# MotorControlBoard_A4988.net
KiCad netlist of a schematic drawn in Altium Designer
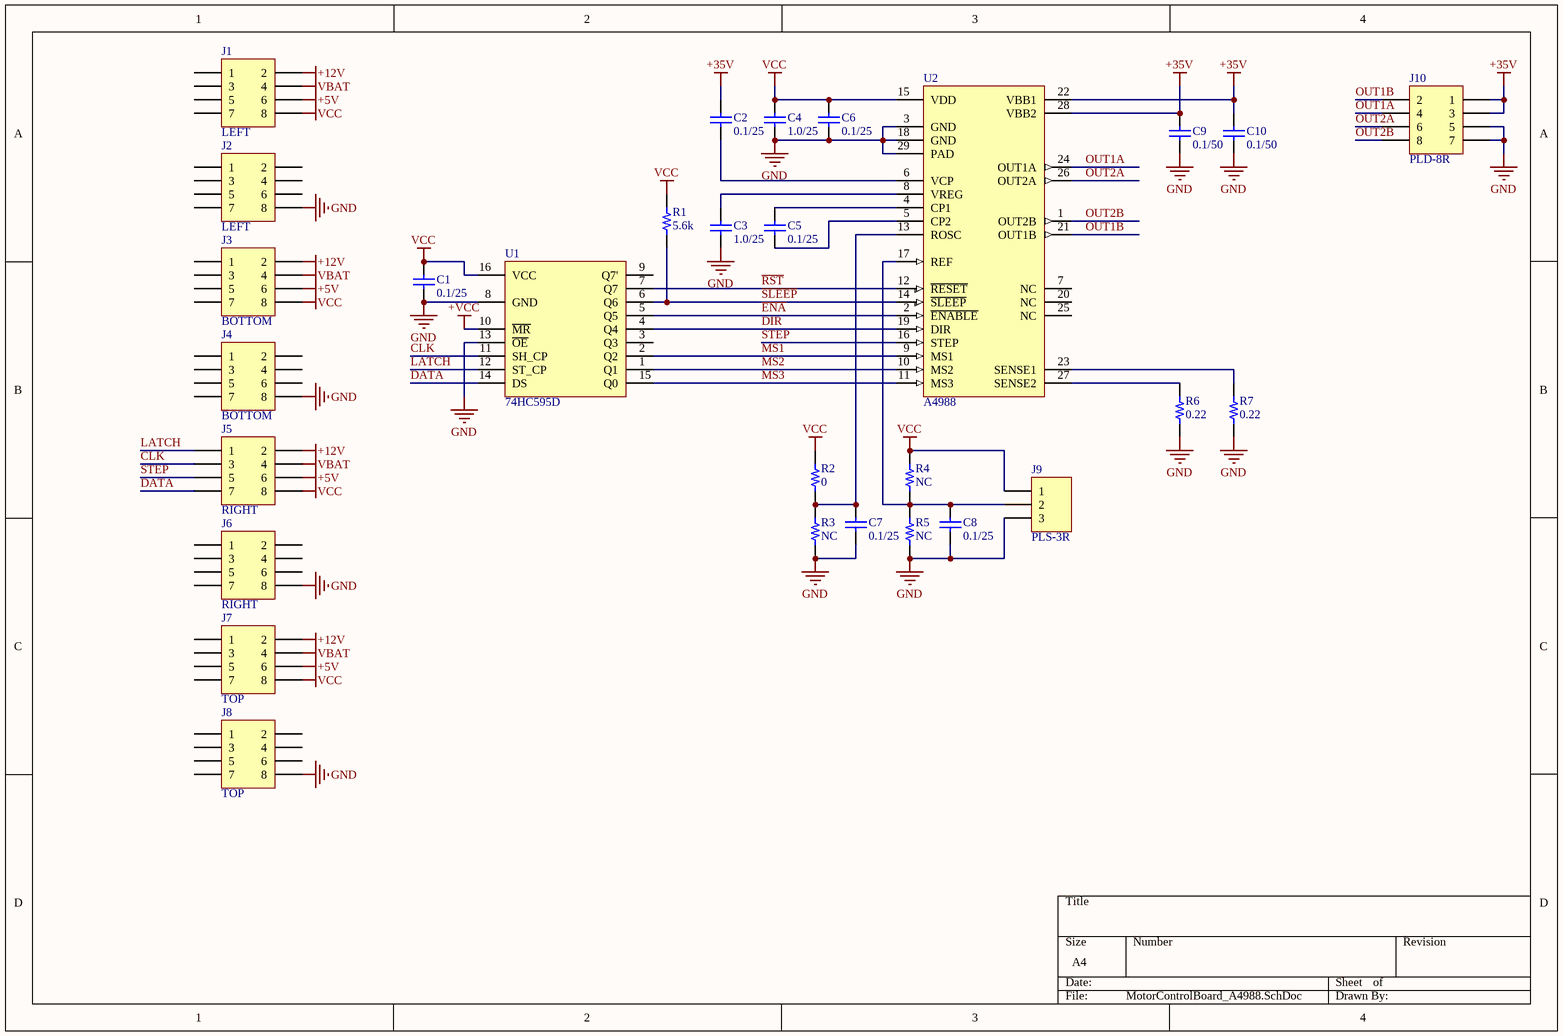
[diagram p0: MotorControlBoard_A4988.SchDoc]

(export (version "E")
  (design (tool "Eeschema 10.0.6"))
  (components
    (comp (ref "C1")
      (value "0.1/25")
      (footprint "CAP0603")
      (description "Ceramic chip capacitor 0603")
      (fields
        (field (name "PARTNUMBER") "CAP0603")
        (field (name "VOLTAGE") "25")
        (field (name "AUTHOR") "oiezhov")
      )
      (libsource (lib "Library") (part "Capacitor"))
    )
    (comp (ref "C2")
      (value "0.1/25")
      (footprint "CAP0402")
      (description "Ceramic chip capacitor 0402")
      (fields
        (field (name "PARTNUMBER") "CAP0402")
        (field (name "VOLTAGE") "25")
        (field (name "AUTHOR") "oiezhov")
      )
      (libsource (lib "Library") (part "Capacitor"))
    )
    (comp (ref "C3")
      (value "1.0/25")
      (footprint "CAP0402")
      (description "Ceramic chip capacitor 0402")
      (fields
        (field (name "PARTNUMBER") "CAP0402")
        (field (name "VOLTAGE") "25")
        (field (name "AUTHOR") "oiezhov")
      )
      (libsource (lib "Library") (part "Capacitor"))
    )
    (comp (ref "C4")
      (value "1.0/25")
      (footprint "CAP0402")
      (description "Ceramic chip capacitor 0402")
      (fields
        (field (name "PARTNUMBER") "CAP0402")
        (field (name "VOLTAGE") "25")
        (field (name "AUTHOR") "oiezhov")
      )
      (libsource (lib "Library") (part "Capacitor"))
    )
    (comp (ref "C5")
      (value "0.1/25")
      (footprint "CAP0402")
      (description "Ceramic chip capacitor 0402")
      (fields
        (field (name "PARTNUMBER") "CAP0402")
        (field (name "VOLTAGE") "25")
        (field (name "AUTHOR") "oiezhov")
      )
      (libsource (lib "Library") (part "Capacitor"))
    )
    (comp (ref "C6")
      (value "0.1/25")
      (footprint "CAP0402")
      (description "Ceramic chip capacitor 0402")
      (fields
        (field (name "PARTNUMBER") "CAP0402")
        (field (name "VOLTAGE") "25")
        (field (name "AUTHOR") "oiezhov")
      )
      (libsource (lib "Library") (part "Capacitor"))
    )
    (comp (ref "C7")
      (value "0.1/25")
      (footprint "CAP0402")
      (description "Ceramic chip capacitor 0402")
      (fields
        (field (name "PARTNUMBER") "CAP0402")
        (field (name "VOLTAGE") "25")
        (field (name "AUTHOR") "oiezhov")
      )
      (libsource (lib "Library") (part "Capacitor"))
    )
    (comp (ref "C8")
      (value "0.1/25")
      (footprint "CAP0402")
      (description "Ceramic chip capacitor 0402")
      (fields
        (field (name "PARTNUMBER") "CAP0402")
        (field (name "VOLTAGE") "25")
        (field (name "AUTHOR") "oiezhov")
      )
      (libsource (lib "Library") (part "Capacitor"))
    )
    (comp (ref "C9")
      (value "0.1/50")
      (footprint "CAP0805")
      (description "Ceramic chip capacitor 0805")
      (fields
        (field (name "PARTNUMBER") "CAP0805")
        (field (name "VOLTAGE") "50")
        (field (name "AUTHOR") "oiezhov")
      )
      (libsource (lib "Library") (part "Capacitor"))
    )
    (comp (ref "C10")
      (value "0.1/50")
      (footprint "CAP0805")
      (description "Ceramic chip capacitor 0805")
      (fields
        (field (name "PARTNUMBER") "CAP0805")
        (field (name "VOLTAGE") "50")
        (field (name "AUTHOR") "oiezhov")
      )
      (libsource (lib "Library") (part "Capacitor"))
    )
    (comp (ref "J1")
      (value "LEFT")
      (footprint "PBDM-8")
      (description "2x4-pin header, pitch 2.54 mm")
      (fields (field (name "PARTNUMBER") "PBDM-8") (field (name "AUTHOR") "oiezhov"))
      (libsource (lib "Library") (part "8-pin dual row connector"))
    )
    (comp (ref "J2")
      (value "LEFT")
      (footprint "PBDM-8")
      (description "2x4-pin header, pitch 2.54 mm")
      (fields (field (name "PARTNUMBER") "PBDM-8") (field (name "AUTHOR") "oiezhov"))
      (libsource (lib "Library") (part "8-pin dual row connector"))
    )
    (comp (ref "J3")
      (value "BOTTOM")
      (footprint "PBDM-8")
      (description "2x4-pin header, pitch 2.54 mm")
      (fields (field (name "PARTNUMBER") "PBDM-8") (field (name "AUTHOR") "oiezhov"))
      (libsource (lib "Library") (part "8-pin dual row connector"))
    )
    (comp (ref "J4")
      (value "BOTTOM")
      (footprint "PBDM-8")
      (description "2x4-pin header, pitch 2.54 mm")
      (fields (field (name "PARTNUMBER") "PBDM-8") (field (name "AUTHOR") "oiezhov"))
      (libsource (lib "Library") (part "8-pin dual row connector"))
    )
    (comp (ref "J5")
      (value "RIGHT")
      (footprint "PBDM-8")
      (description "2x4-pin header, pitch 2.54 mm")
      (fields (field (name "PARTNUMBER") "PBDM-8") (field (name "AUTHOR") "oiezhov"))
      (libsource (lib "Library") (part "8-pin dual row connector"))
    )
    (comp (ref "J6")
      (value "RIGHT")
      (footprint "PBDM-8")
      (description "2x4-pin header, pitch 2.54 mm")
      (fields (field (name "PARTNUMBER") "PBDM-8") (field (name "AUTHOR") "oiezhov"))
      (libsource (lib "Library") (part "8-pin dual row connector"))
    )
    (comp (ref "J7")
      (value "TOP")
      (footprint "PBDM-8")
      (description "2x4-pin header, pitch 2.54 mm")
      (fields (field (name "PARTNUMBER") "PBDM-8") (field (name "AUTHOR") "oiezhov"))
      (libsource (lib "Library") (part "8-pin dual row connector"))
    )
    (comp (ref "J8")
      (value "TOP")
      (footprint "PBDM-8")
      (description "2x4-pin header, pitch 2.54 mm")
      (fields (field (name "PARTNUMBER") "PBDM-8") (field (name "AUTHOR") "oiezhov"))
      (libsource (lib "Library") (part "8-pin dual row connector"))
    )
    (comp (ref "J9")
      (value "PLS-3R")
      (footprint "PLS-3R")
      (description "3-pin angle header, pitch 2.54 mm")
      (fields (field (name "AUTHOR") "oiezhov"))
      (libsource (lib "Library") (part "3-pin connector"))
    )
    (comp (ref "J10")
      (value "PLD-8R")
      (footprint "PLD-8R")
      (description "2x4-pin angle header, pitch 2.54 mm")
      (fields (field (name "AUTHOR") "oiezhov"))
      (libsource (lib "") (part "8-pin dual row connector_1"))
    )
    (comp (ref "R1")
      (value "5.6k")
      (footprint "RES0402")
      (description "Ceramic chip resistor")
      (fields (field (name "PARTNUMBER") "RES0402") (field (name "AUTHOR") "oiezhov"))
      (libsource (lib "Library") (part "Resistor"))
    )
    (comp (ref "R2")
      (value "0")
      (footprint "RES0402")
      (description "Ceramic chip resistor")
      (fields (field (name "PARTNUMBER") "RES0402") (field (name "AUTHOR") "oiezhov"))
      (libsource (lib "Library") (part "Resistor"))
    )
    (comp (ref "R3")
      (value "NC")
      (footprint "RES0402")
      (description "Ceramic chip resistor")
      (fields (field (name "PARTNUMBER") "RES0402") (field (name "AUTHOR") "oiezhov"))
      (libsource (lib "Library") (part "Resistor"))
    )
    (comp (ref "R4")
      (value "NC")
      (footprint "RES0402")
      (description "Ceramic chip resistor")
      (fields (field (name "PARTNUMBER") "RES0402") (field (name "AUTHOR") "oiezhov"))
      (libsource (lib "Library") (part "Resistor"))
    )
    (comp (ref "R5")
      (value "NC")
      (footprint "RES0402")
      (description "Ceramic chip resistor")
      (fields (field (name "PARTNUMBER") "RES0402") (field (name "AUTHOR") "oiezhov"))
      (libsource (lib "Library") (part "Resistor"))
    )
    (comp (ref "R6")
      (value "0.22")
      (footprint "RES2512")
      (description "Ceramic chip resistor")
      (fields (field (name "PARTNUMBER") "RES2512") (field (name "AUTHOR") "oiezhov"))
      (libsource (lib "Library") (part "Resistor"))
    )
    (comp (ref "R7")
      (value "0.22")
      (footprint "RES2512")
      (description "Ceramic chip resistor")
      (fields (field (name "PARTNUMBER") "RES2512") (field (name "AUTHOR") "oiezhov"))
      (libsource (lib "Library") (part "Resistor"))
    )
    (comp (ref "U1")
      (value "74HC595D")
      (footprint "SO16")
      (description "8-bit serial-in, serial or parallel-out shift register with output latches; 3-state")
      (fields (field (name "AUTHOR") "oiezhov"))
      (libsource (lib "Library") (part "74595"))
    )
    (comp (ref "U2")
      (value "A4988")
      (footprint "QFN28-0.5")
      (description "DMOS Microstepping Driver with Translator And Overcurrent Protection")
      (fields (field (name "AUTHOR") "oiezhov"))
      (libsource (lib "Library") (part "A4988"))
    )
  )
  (nets
    (net (code "1") (name "+5V") (class "Default")
      (node (ref "J1") (pin "6") (pinfunction "6_6") (pintype "passive"))
      (node (ref "J3") (pin "6") (pinfunction "6_6") (pintype "passive"))
      (node (ref "J5") (pin "6") (pinfunction "6_6") (pintype "passive"))
      (node (ref "J7") (pin "6") (pinfunction "6_6") (pintype "passive"))
    )
    (net (code "2") (name "+12V") (class "Default")
      (node (ref "J1") (pin "2") (pinfunction "2_2") (pintype "passive"))
      (node (ref "J3") (pin "2") (pinfunction "2_2") (pintype "passive"))
      (node (ref "J5") (pin "2") (pinfunction "2_2") (pintype "passive"))
      (node (ref "J7") (pin "2") (pinfunction "2_2") (pintype "passive"))
    )
    (net (code "3") (name "+35V") (class "Default")
      (node (ref "C10") (pin "2") (pinfunction "2_2") (pintype "passive"))
      (node (ref "C2") (pin "2") (pinfunction "2_2") (pintype "passive"))
      (node (ref "C9") (pin "2") (pinfunction "2_2") (pintype "passive"))
      (node (ref "J10") (pin "1") (pinfunction "1_1") (pintype "passive"))
      (node (ref "J10") (pin "3") (pinfunction "3_3") (pintype "passive"))
      (node (ref "U2") (pin "22") (pinfunction "VBB1_22") (pintype "power_in"))
      (node (ref "U2") (pin "28") (pinfunction "VBB2_28") (pintype "power_in"))
    )
    (net (code "4") (name "+VCC") (class "Default")
      (node (ref "U1") (pin "10") (pinfunction "~{MR}_10") (pintype "passive"))
    )
    (net (code "5") (name "/CLK") (class "Default")
      (node (ref "J5") (pin "3") (pinfunction "3_3") (pintype "passive"))
      (node (ref "U1") (pin "11") (pinfunction "SH_CP_11") (pintype "passive"))
    )
    (net (code "6") (name "/DATA") (class "Default")
      (node (ref "J5") (pin "7") (pinfunction "7_7") (pintype "passive"))
      (node (ref "U1") (pin "14") (pinfunction "DS_14") (pintype "passive"))
    )
    (net (code "7") (name "/DIR") (class "Default")
      (node (ref "U1") (pin "4") (pinfunction "Q4_4") (pintype "passive"))
      (node (ref "U2") (pin "19") (pinfunction "DIR_19") (pintype "input"))
    )
    (net (code "8") (name "/LATCH") (class "Default")
      (node (ref "J5") (pin "1") (pinfunction "1_1") (pintype "passive"))
      (node (ref "U1") (pin "12") (pinfunction "ST_CP_12") (pintype "passive"))
    )
    (net (code "9") (name "/MS1") (class "Default")
      (node (ref "U1") (pin "2") (pinfunction "Q2_2") (pintype "passive"))
      (node (ref "U2") (pin "9") (pinfunction "MS1_9") (pintype "input"))
    )
    (net (code "10") (name "/MS2") (class "Default")
      (node (ref "U1") (pin "1") (pinfunction "Q1_1") (pintype "passive"))
      (node (ref "U2") (pin "10") (pinfunction "MS2_10") (pintype "input"))
    )
    (net (code "11") (name "/MS3") (class "Default")
      (node (ref "U1") (pin "15") (pinfunction "Q0_15") (pintype "passive"))
      (node (ref "U2") (pin "11") (pinfunction "MS3_11") (pintype "input"))
    )
    (net (code "12") (name "/OUT1A") (class "Default")
      (node (ref "J10") (pin "4") (pinfunction "4_4") (pintype "passive"))
      (node (ref "U2") (pin "24") (pinfunction "OUT1A_24") (pintype "output"))
    )
    (net (code "13") (name "/OUT1B") (class "Default")
      (node (ref "J10") (pin "2") (pinfunction "2_2") (pintype "passive"))
      (node (ref "U2") (pin "21") (pinfunction "OUT1B_21") (pintype "output"))
    )
    (net (code "14") (name "/OUT2A") (class "Default")
      (node (ref "J10") (pin "6") (pinfunction "6_6") (pintype "passive"))
      (node (ref "U2") (pin "26") (pinfunction "OUT2A_26") (pintype "output"))
    )
    (net (code "15") (name "/OUT2B") (class "Default")
      (node (ref "J10") (pin "8") (pinfunction "8_8") (pintype "passive"))
      (node (ref "U2") (pin "1") (pinfunction "OUT2B_1") (pintype "output"))
    )
    (net (code "16") (name "/STEP") (class "Default")
      (node (ref "J5") (pin "5") (pinfunction "5_5") (pintype "passive"))
      (node (ref "U2") (pin "16") (pinfunction "STEP_16") (pintype "input"))
    )
    (net (code "17") (name "/~{ENA}") (class "Default")
      (node (ref "U1") (pin "5") (pinfunction "Q5_5") (pintype "passive"))
      (node (ref "U2") (pin "2") (pinfunction "~{ENABLE}_2") (pintype "input"))
    )
    (net (code "18") (name "/~{RST}") (class "Default")
      (node (ref "U1") (pin "7") (pinfunction "Q7_7") (pintype "passive"))
      (node (ref "U2") (pin "12") (pinfunction "~{RESET}_12") (pintype "input"))
    )
    (net (code "19") (name "/~{SLEEP}") (class "Default")
      (node (ref "R1") (pin "2") (pinfunction "2_2") (pintype "passive"))
      (node (ref "U1") (pin "6") (pinfunction "Q6_6") (pintype "passive"))
      (node (ref "U2") (pin "14") (pinfunction "~{SLEEP}_14") (pintype "input"))
    )
    (net (code "20") (name "GND") (class "Default")
      (node (ref "C1") (pin "1") (pinfunction "1_1") (pintype "passive"))
      (node (ref "C10") (pin "1") (pinfunction "1_1") (pintype "passive"))
      (node (ref "C3") (pin "1") (pinfunction "1_1") (pintype "passive"))
      (node (ref "C4") (pin "1") (pinfunction "1_1") (pintype "passive"))
      (node (ref "C6") (pin "1") (pinfunction "1_1") (pintype "passive"))
      (node (ref "C7") (pin "1") (pinfunction "1_1") (pintype "passive"))
      (node (ref "C8") (pin "1") (pinfunction "1_1") (pintype "passive"))
      (node (ref "C9") (pin "1") (pinfunction "1_1") (pintype "passive"))
      (node (ref "J10") (pin "5") (pinfunction "5_5") (pintype "passive"))
      (node (ref "J10") (pin "7") (pinfunction "7_7") (pintype "passive"))
      (node (ref "J2") (pin "8") (pinfunction "8_8") (pintype "passive"))
      (node (ref "J4") (pin "8") (pinfunction "8_8") (pintype "passive"))
      (node (ref "J6") (pin "8") (pinfunction "8_8") (pintype "passive"))
      (node (ref "J8") (pin "8") (pinfunction "8_8") (pintype "passive"))
      (node (ref "J9") (pin "3") (pinfunction "3_3") (pintype "passive"))
      (node (ref "R3") (pin "2") (pinfunction "2_2") (pintype "passive"))
      (node (ref "R5") (pin "2") (pinfunction "2_2") (pintype "passive"))
      (node (ref "R6") (pin "1") (pinfunction "1_1") (pintype "passive"))
      (node (ref "R7") (pin "1") (pinfunction "1_1") (pintype "passive"))
      (node (ref "U1") (pin "13") (pinfunction "~{OE}_13") (pintype "passive"))
      (node (ref "U1") (pin "8") (pinfunction "GND_8") (pintype "passive"))
      (node (ref "U2") (pin "18") (pinfunction "GND_18") (pintype "power_in"))
      (node (ref "U2") (pin "29") (pinfunction "PAD_29") (pintype "power_in"))
      (node (ref "U2") (pin "3") (pinfunction "GND_3") (pintype "power_in"))
    )
    (net (code "21") (name "Net-(U2-CP1)") (class "Default")
      (node (ref "C5") (pin "2") (pinfunction "2_2") (pintype "passive"))
      (node (ref "U2") (pin "4") (pinfunction "CP1_4") (pintype "passive"))
    )
    (net (code "22") (name "Net-(U2-CP2)") (class "Default")
      (node (ref "C5") (pin "1") (pinfunction "1_1") (pintype "passive"))
      (node (ref "U2") (pin "5") (pinfunction "CP2_5") (pintype "passive"))
    )
    (net (code "23") (name "Net-(U2-REF)") (class "Default")
      (node (ref "C8") (pin "2") (pinfunction "2_2") (pintype "passive"))
      (node (ref "J9") (pin "2") (pinfunction "2_2") (pintype "passive"))
      (node (ref "R4") (pin "2") (pinfunction "2_2") (pintype "passive"))
      (node (ref "R5") (pin "1") (pinfunction "1_1") (pintype "passive"))
      (node (ref "U2") (pin "17") (pinfunction "REF_17") (pintype "input"))
    )
    (net (code "24") (name "Net-(U2-ROSC)") (class "Default")
      (node (ref "C7") (pin "2") (pinfunction "2_2") (pintype "passive"))
      (node (ref "R2") (pin "2") (pinfunction "2_2") (pintype "passive"))
      (node (ref "R3") (pin "1") (pinfunction "1_1") (pintype "passive"))
      (node (ref "U2") (pin "13") (pinfunction "ROSC_13") (pintype "passive"))
    )
    (net (code "25") (name "Net-(U2-SENSE1)") (class "Default")
      (node (ref "R7") (pin "2") (pinfunction "2_2") (pintype "passive"))
      (node (ref "U2") (pin "23") (pinfunction "SENSE1_23") (pintype "passive"))
    )
    (net (code "26") (name "Net-(U2-SENSE2)") (class "Default")
      (node (ref "R6") (pin "2") (pinfunction "2_2") (pintype "passive"))
      (node (ref "U2") (pin "27") (pinfunction "SENSE2_27") (pintype "passive"))
    )
    (net (code "27") (name "Net-(U2-VCP)") (class "Default")
      (node (ref "C2") (pin "1") (pinfunction "1_1") (pintype "passive"))
      (node (ref "U2") (pin "6") (pinfunction "VCP_6") (pintype "power_in"))
    )
    (net (code "28") (name "Net-(U2-VREG)") (class "Default")
      (node (ref "C3") (pin "2") (pinfunction "2_2") (pintype "passive"))
      (node (ref "U2") (pin "8") (pinfunction "VREG_8") (pintype "power_in"))
    )
    (net (code "29") (name "VBAT") (class "Default")
      (node (ref "J1") (pin "4") (pinfunction "4_4") (pintype "passive"))
      (node (ref "J3") (pin "4") (pinfunction "4_4") (pintype "passive"))
      (node (ref "J5") (pin "4") (pinfunction "4_4") (pintype "passive"))
      (node (ref "J7") (pin "4") (pinfunction "4_4") (pintype "passive"))
    )
    (net (code "30") (name "VCC") (class "Default")
      (node (ref "C1") (pin "2") (pinfunction "2_2") (pintype "passive"))
      (node (ref "C4") (pin "2") (pinfunction "2_2") (pintype "passive"))
      (node (ref "C6") (pin "2") (pinfunction "2_2") (pintype "passive"))
      (node (ref "J1") (pin "8") (pinfunction "8_8") (pintype "passive"))
      (node (ref "J3") (pin "8") (pinfunction "8_8") (pintype "passive"))
      (node (ref "J5") (pin "8") (pinfunction "8_8") (pintype "passive"))
      (node (ref "J7") (pin "8") (pinfunction "8_8") (pintype "passive"))
      (node (ref "J9") (pin "1") (pinfunction "1_1") (pintype "passive"))
      (node (ref "R1") (pin "1") (pinfunction "1_1") (pintype "passive"))
      (node (ref "R2") (pin "1") (pinfunction "1_1") (pintype "passive"))
      (node (ref "R4") (pin "1") (pinfunction "1_1") (pintype "passive"))
      (node (ref "U1") (pin "16") (pinfunction "VCC_16") (pintype "passive"))
      (node (ref "U2") (pin "15") (pinfunction "VDD_15") (pintype "power_in"))
    )
    (net (code "31") (name "unconnected-(J1-Pad1)") (class "Default")
      (node (ref "J1") (pin "1") (pinfunction "1_1") (pintype "passive"))
    )
    (net (code "32") (name "unconnected-(J1-Pad3)") (class "Default")
      (node (ref "J1") (pin "3") (pinfunction "3_3") (pintype "passive"))
    )
    (net (code "33") (name "unconnected-(J1-Pad5)") (class "Default")
      (node (ref "J1") (pin "5") (pinfunction "5_5") (pintype "passive"))
    )
    (net (code "34") (name "unconnected-(J1-Pad7)") (class "Default")
      (node (ref "J1") (pin "7") (pinfunction "7_7") (pintype "passive"))
    )
    (net (code "35") (name "unconnected-(J2-Pad1)") (class "Default")
      (node (ref "J2") (pin "1") (pinfunction "1_1") (pintype "passive"))
    )
    (net (code "36") (name "unconnected-(J2-Pad2)") (class "Default")
      (node (ref "J2") (pin "2") (pinfunction "2_2") (pintype "passive"))
    )
    (net (code "37") (name "unconnected-(J2-Pad3)") (class "Default")
      (node (ref "J2") (pin "3") (pinfunction "3_3") (pintype "passive"))
    )
    (net (code "38") (name "unconnected-(J2-Pad4)") (class "Default")
      (node (ref "J2") (pin "4") (pinfunction "4_4") (pintype "passive"))
    )
    (net (code "39") (name "unconnected-(J2-Pad5)") (class "Default")
      (node (ref "J2") (pin "5") (pinfunction "5_5") (pintype "passive"))
    )
    (net (code "40") (name "unconnected-(J2-Pad6)") (class "Default")
      (node (ref "J2") (pin "6") (pinfunction "6_6") (pintype "passive"))
    )
    (net (code "41") (name "unconnected-(J2-Pad7)") (class "Default")
      (node (ref "J2") (pin "7") (pinfunction "7_7") (pintype "passive"))
    )
    (net (code "42") (name "unconnected-(J3-Pad1)") (class "Default")
      (node (ref "J3") (pin "1") (pinfunction "1_1") (pintype "passive"))
    )
    (net (code "43") (name "unconnected-(J3-Pad3)") (class "Default")
      (node (ref "J3") (pin "3") (pinfunction "3_3") (pintype "passive"))
    )
    (net (code "44") (name "unconnected-(J3-Pad5)") (class "Default")
      (node (ref "J3") (pin "5") (pinfunction "5_5") (pintype "passive"))
    )
    (net (code "45") (name "unconnected-(J3-Pad7)") (class "Default")
      (node (ref "J3") (pin "7") (pinfunction "7_7") (pintype "passive"))
    )
    (net (code "46") (name "unconnected-(J4-Pad1)") (class "Default")
      (node (ref "J4") (pin "1") (pinfunction "1_1") (pintype "passive"))
    )
    (net (code "47") (name "unconnected-(J4-Pad2)") (class "Default")
      (node (ref "J4") (pin "2") (pinfunction "2_2") (pintype "passive"))
    )
    (net (code "48") (name "unconnected-(J4-Pad3)") (class "Default")
      (node (ref "J4") (pin "3") (pinfunction "3_3") (pintype "passive"))
    )
    (net (code "49") (name "unconnected-(J4-Pad4)") (class "Default")
      (node (ref "J4") (pin "4") (pinfunction "4_4") (pintype "passive"))
    )
    (net (code "50") (name "unconnected-(J4-Pad5)") (class "Default")
      (node (ref "J4") (pin "5") (pinfunction "5_5") (pintype "passive"))
    )
    (net (code "51") (name "unconnected-(J4-Pad6)") (class "Default")
      (node (ref "J4") (pin "6") (pinfunction "6_6") (pintype "passive"))
    )
    (net (code "52") (name "unconnected-(J4-Pad7)") (class "Default")
      (node (ref "J4") (pin "7") (pinfunction "7_7") (pintype "passive"))
    )
    (net (code "53") (name "unconnected-(J6-Pad1)") (class "Default")
      (node (ref "J6") (pin "1") (pinfunction "1_1") (pintype "passive"))
    )
    (net (code "54") (name "unconnected-(J6-Pad2)") (class "Default")
      (node (ref "J6") (pin "2") (pinfunction "2_2") (pintype "passive"))
    )
    (net (code "55") (name "unconnected-(J6-Pad3)") (class "Default")
      (node (ref "J6") (pin "3") (pinfunction "3_3") (pintype "passive"))
    )
    (net (code "56") (name "unconnected-(J6-Pad4)") (class "Default")
      (node (ref "J6") (pin "4") (pinfunction "4_4") (pintype "passive"))
    )
    (net (code "57") (name "unconnected-(J6-Pad5)") (class "Default")
      (node (ref "J6") (pin "5") (pinfunction "5_5") (pintype "passive"))
    )
    (net (code "58") (name "unconnected-(J6-Pad6)") (class "Default")
      (node (ref "J6") (pin "6") (pinfunction "6_6") (pintype "passive"))
    )
    (net (code "59") (name "unconnected-(J6-Pad7)") (class "Default")
      (node (ref "J6") (pin "7") (pinfunction "7_7") (pintype "passive"))
    )
    (net (code "60") (name "unconnected-(J7-Pad1)") (class "Default")
      (node (ref "J7") (pin "1") (pinfunction "1_1") (pintype "passive"))
    )
    (net (code "61") (name "unconnected-(J7-Pad3)") (class "Default")
      (node (ref "J7") (pin "3") (pinfunction "3_3") (pintype "passive"))
    )
    (net (code "62") (name "unconnected-(J7-Pad5)") (class "Default")
      (node (ref "J7") (pin "5") (pinfunction "5_5") (pintype "passive"))
    )
    (net (code "63") (name "unconnected-(J7-Pad7)") (class "Default")
      (node (ref "J7") (pin "7") (pinfunction "7_7") (pintype "passive"))
    )
    (net (code "64") (name "unconnected-(J8-Pad1)") (class "Default")
      (node (ref "J8") (pin "1") (pinfunction "1_1") (pintype "passive"))
    )
    (net (code "65") (name "unconnected-(J8-Pad2)") (class "Default")
      (node (ref "J8") (pin "2") (pinfunction "2_2") (pintype "passive"))
    )
    (net (code "66") (name "unconnected-(J8-Pad3)") (class "Default")
      (node (ref "J8") (pin "3") (pinfunction "3_3") (pintype "passive"))
    )
    (net (code "67") (name "unconnected-(J8-Pad4)") (class "Default")
      (node (ref "J8") (pin "4") (pinfunction "4_4") (pintype "passive"))
    )
    (net (code "68") (name "unconnected-(J8-Pad5)") (class "Default")
      (node (ref "J8") (pin "5") (pinfunction "5_5") (pintype "passive"))
    )
    (net (code "69") (name "unconnected-(J8-Pad6)") (class "Default")
      (node (ref "J8") (pin "6") (pinfunction "6_6") (pintype "passive"))
    )
    (net (code "70") (name "unconnected-(J8-Pad7)") (class "Default")
      (node (ref "J8") (pin "7") (pinfunction "7_7") (pintype "passive"))
    )
    (net (code "71") (name "unconnected-(U1-Q3-Pad3)") (class "Default")
      (node (ref "U1") (pin "3") (pinfunction "Q3_3") (pintype "passive"))
    )
    (net (code "72") (name "unconnected-(U1-Q7'-Pad9)") (class "Default")
      (node (ref "U1") (pin "9") (pinfunction "Q7'_9") (pintype "passive"))
    )
    (net (code "73") (name "unconnected-(U2-NC-Pad7)") (class "Default")
      (node (ref "U2") (pin "7") (pinfunction "NC_7") (pintype "passive"))
    )
    (net (code "74") (name "unconnected-(U2-NC-Pad20)") (class "Default")
      (node (ref "U2") (pin "20") (pinfunction "NC_20") (pintype "passive"))
    )
    (net (code "75") (name "unconnected-(U2-NC-Pad25)") (class "Default")
      (node (ref "U2") (pin "25") (pinfunction "NC_25") (pintype "passive"))
    )
  )
)
